# WWOL_main.net
KiCad netlist of a schematic drawn in Altium Designer
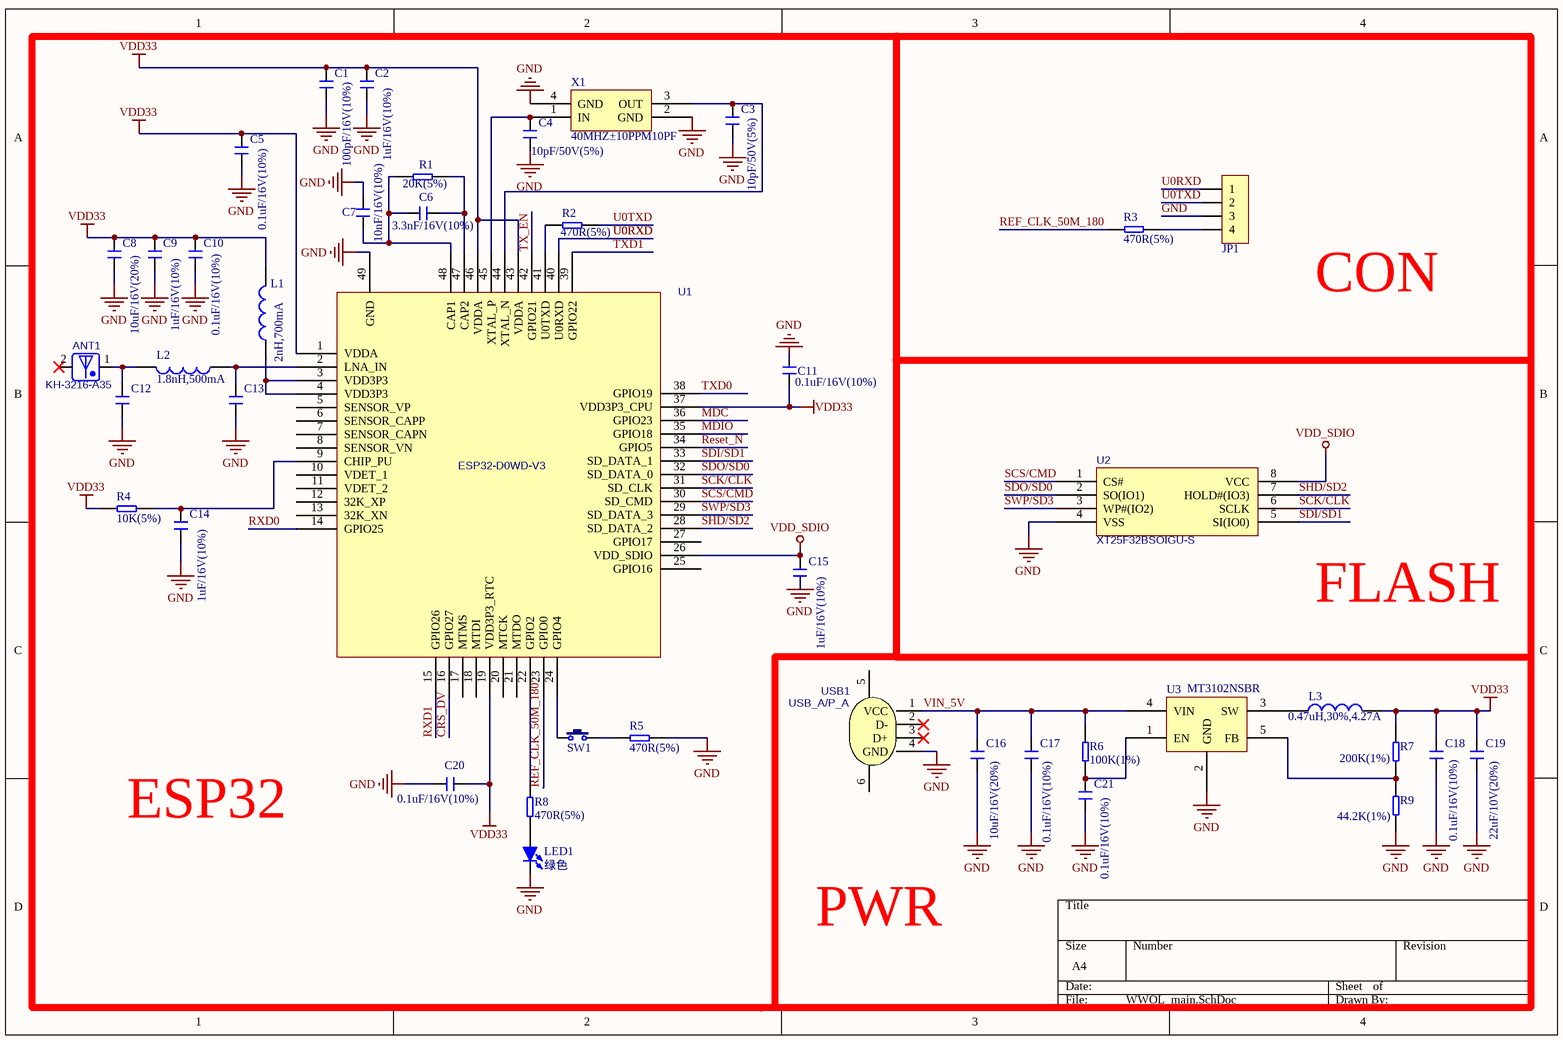
[diagram p0: WWOL_main.SchDoc]

(export (version "E")
  (design (tool "Eeschema 10.0.6"))
  (components
    (comp (ref "ANT1")
      (value "KH-3216-A35")
      (footprint "ANT-SMD-2_L3.2-W1.6-C504002")
      (description "金航标 KH-3216-A35")
      (fields (field (name "BOM_SUPPLIER PART") "C504002") (field (name "CONTRIBUTOR") "LCSC"))
      (libsource (lib "WWOL") (part "KH-3216-A35"))
    )
    (comp (ref "C1")
      (value "100pF/16V(10%)")
      (footprint "C0402")
      (description "无极性贴片电容")
      (fields (field (name "版权归属") "源创客"))
      (libsource (lib "WWOL") (part "C"))
    )
    (comp (ref "C2")
      (value "1uF/16V(10%)")
      (footprint "C0402")
      (description "无极性贴片电容")
      (fields (field (name "版权归属") "源创客"))
      (libsource (lib "WWOL") (part "C"))
    )
    (comp (ref "C3")
      (value "10pF/50V(5%)")
      (footprint "C0402")
      (description "无极性贴片电容")
      (fields (field (name "版权归属") "源创客"))
      (libsource (lib "WWOL") (part "C"))
    )
    (comp (ref "C4")
      (value "10pF/50V(5%)")
      (footprint "C0402")
      (description "无极性贴片电容")
      (fields (field (name "版权归属") "源创客"))
      (libsource (lib "WWOL") (part "C"))
    )
    (comp (ref "C5")
      (value "0.1uF/16V(10%)")
      (footprint "C0402")
      (description "无极性贴片电容")
      (fields (field (name "版权归属") "源创客"))
      (libsource (lib "WWOL") (part "C"))
    )
    (comp (ref "C6")
      (value "3.3nF/16V(10%)")
      (footprint "C0402")
      (description "无极性贴片电容")
      (fields (field (name "版权归属") "源创客"))
      (libsource (lib "WWOL") (part "C"))
    )
    (comp (ref "C7")
      (value "10nF/16V(10%)")
      (footprint "C0402")
      (description "无极性贴片电容")
      (fields (field (name "版权归属") "源创客"))
      (libsource (lib "WWOL") (part "C"))
    )
    (comp (ref "C8")
      (value "10uF/16V(20%)")
      (footprint "C0402")
      (description "无极性贴片电容")
      (fields (field (name "版权归属") "源创客"))
      (libsource (lib "WWOL") (part "C"))
    )
    (comp (ref "C9")
      (value "1uF/16V(10%)")
      (footprint "C0402")
      (description "无极性贴片电容")
      (fields (field (name "版权归属") "源创客"))
      (libsource (lib "WWOL") (part "C"))
    )
    (comp (ref "C10")
      (value "0.1uF/16V(10%)")
      (footprint "C0402")
      (description "无极性贴片电容")
      (fields (field (name "版权归属") "源创客"))
      (libsource (lib "WWOL") (part "C"))
    )
    (comp (ref "C11")
      (value "0.1uF/16V(10%)")
      (footprint "C0402")
      (description "无极性贴片电容")
      (fields (field (name "版权归属") "源创客"))
      (libsource (lib "WWOL") (part "C"))
    )
    (comp (ref "C12")
      (value "~")
      (footprint "C0402")
      (description "无极性贴片电容")
      (fields (field (name "版权归属") "源创客"))
      (libsource (lib "WWOL") (part "C"))
    )
    (comp (ref "C13")
      (value "~")
      (footprint "C0402")
      (description "无极性贴片电容")
      (fields (field (name "版权归属") "源创客"))
      (libsource (lib "WWOL") (part "C"))
    )
    (comp (ref "C14")
      (value "1uF/16V(10%)")
      (footprint "C0402")
      (description "无极性贴片电容")
      (fields (field (name "版权归属") "源创客"))
      (libsource (lib "WWOL") (part "C"))
    )
    (comp (ref "C15")
      (value "1uF/16V(10%)")
      (footprint "C0402")
      (description "无极性贴片电容")
      (fields (field (name "版权归属") "源创客"))
      (libsource (lib "WWOL") (part "C"))
    )
    (comp (ref "C16")
      (value "10uF/16V(20%)")
      (footprint "C0402")
      (description "无极性贴片电容")
      (fields (field (name "版权归属") "源创客"))
      (libsource (lib "WWOL") (part "C"))
    )
    (comp (ref "C17")
      (value "0.1uF/16V(10%)")
      (footprint "C0402")
      (description "无极性贴片电容")
      (fields (field (name "版权归属") "源创客"))
      (libsource (lib "WWOL") (part "C"))
    )
    (comp (ref "C18")
      (value "0.1uF/16V(10%)")
      (footprint "C0402")
      (description "无极性贴片电容")
      (fields (field (name "版权归属") "源创客"))
      (libsource (lib "WWOL") (part "C"))
    )
    (comp (ref "C19")
      (value "22uF/10V(20%)")
      (footprint "C0402")
      (description "无极性贴片电容")
      (fields (field (name "版权归属") "源创客"))
      (libsource (lib "WWOL") (part "C"))
    )
    (comp (ref "C20")
      (value "0.1uF/16V(10%)")
      (footprint "C0402")
      (description "无极性贴片电容")
      (fields (field (name "版权归属") "源创客"))
      (libsource (lib "WWOL") (part "C"))
    )
    (comp (ref "C21")
      (value "0.1uF/16V(10%)")
      (footprint "C0402")
      (description "无极性贴片电容")
      (fields (field (name "版权归属") "源创客"))
      (libsource (lib "WWOL") (part "C"))
    )
    (comp (ref "JP1")
      (value "HDR-1X4")
      (footprint "HDR2.54-LI-4P")
      (description "4P接插件")
      (fields (field (name "版权归属") "源创客"))
      (libsource (lib "WWOL") (part "Header 4"))
    )
    (comp (ref "L1")
      (value "2nH,700mA")
      (footprint "L0402")
      (description "小功率贴片电感")
      (libsource (lib "WWOL") (part "L"))
    )
    (comp (ref "L2")
      (value "1.8nH,500mA")
      (footprint "L0402")
      (description "小功率贴片电感")
      (libsource (lib "WWOL") (part "L"))
    )
    (comp (ref "L3")
      (value "0.47uH,30%,4.27A")
      (footprint "NR2520")
      (description "muRata(村田) DFE252012F-4R7M=P2")
      (libsource (lib "WWOL") (part "L"))
    )
    (comp (ref "LED1")
      (value "绿色")
      (footprint "LED 0402G")
      (description "贴片LED")
      (fields (field (name "版权归属") "源创客"))
      (libsource (lib "WWOL") (part "LED-SMD"))
    )
    (comp (ref "R1")
      (value "20K(5%)")
      (footprint "R0402")
      (description "贴片电阻")
      (libsource (lib "WWOL") (part "R"))
    )
    (comp (ref "R2")
      (value "470R(5%)")
      (footprint "R0402")
      (description "贴片电阻")
      (libsource (lib "WWOL") (part "R"))
    )
    (comp (ref "R3")
      (value "470R(5%)")
      (footprint "R0402")
      (description "贴片电阻")
      (libsource (lib "WWOL") (part "R"))
    )
    (comp (ref "R4")
      (value "10K(5%)")
      (footprint "R0402")
      (description "贴片电阻")
      (libsource (lib "WWOL") (part "R"))
    )
    (comp (ref "R5")
      (value "470R(5%)")
      (footprint "R0402")
      (description "贴片电阻")
      (libsource (lib "WWOL") (part "R"))
    )
    (comp (ref "R6")
      (value "100K(1%)")
      (footprint "R0402")
      (description "贴片电阻")
      (libsource (lib "WWOL") (part "R"))
    )
    (comp (ref "R7")
      (value "200K(1%)")
      (footprint "R0402")
      (description "贴片电阻")
      (libsource (lib "WWOL") (part "R"))
    )
    (comp (ref "R8")
      (value "470R(5%)")
      (footprint "R0402")
      (description "贴片电阻")
      (libsource (lib "WWOL") (part "R"))
    )
    (comp (ref "R9")
      (value "44.2K(1%)")
      (footprint "R0402")
      (description "贴片电阻")
      (libsource (lib "WWOL") (part "R"))
    )
    (comp (ref "SW1")
      (value "TSW SMD-3*6*2.5")
      (footprint "TSW SMD-3*6*2.5")
      (description "3x6轻触开关")
      (fields (field (name "版权归属") "源创客"))
      (libsource (lib "WWOL") (part "TSW 3x6"))
    )
    (comp (ref "U1")
      (value "ESP32-D0WD-V3")
      (footprint "QFN35P500X500X90_HS-49N")
      (fields (field (name "BOM_SUPPLIER PART") "C967021") (field (name "CONTRIBUTOR") "LCSC"))
      (libsource (lib "WWOL") (part "ESP32-D0WD-V3"))
    )
    (comp (ref "U2")
      (value "XT25F32BSOIGU-S")
      (footprint "SOP127P600X175-8N")
      (description "spi flash")
      (fields (field (name "BOM_SUPPLIER PART") "C558851") (field (name "CONTRIBUTOR") "LCSC"))
      (libsource (lib "WWOL") (part "XT25F32BSOIGU-S"))
    )
    (comp (ref "U3")
      (value "MT3102NSBR")
      (footprint "SOT95P280X145-5N")
      (description "开关电源")
      (libsource (lib "WWOL") (part "MT3102NSBR"))
    )
    (comp (ref "USB1")
      (value "USB_A/P_A")
      (footprint "USB_A/P_A")
      (description "精拓金 917-181A102ED60200")
      (fields
        (field (name "BOM_SUPPLIER PART") "C183610")
        (field (name "BOM_MANUFACTURER PART") "USB-07")
        (field (name "CONTRIBUTOR") "LCSC")
      )
      (libsource (lib "WWOL") (part "USB_A/P_A"))
    )
    (comp (ref "X1")
      (value "40MHZ±10PPM10PF")
      (footprint "SMD2520-4P")
      (description "无源晶振")
      (libsource (lib "WWOL") (part "XTAL-4P"))
    )
  )
  (nets
    (net (code "1") (name "/CRS_DV") (class "Default")
      (node (ref "U1") (pin "16") (pinfunction "GPIO27_16") (pintype "passive"))
    )
    (net (code "2") (name "/MDC") (class "Default")
      (node (ref "U1") (pin "36") (pinfunction "GPIO23_36") (pintype "passive"))
    )
    (net (code "3") (name "/MDIO") (class "Default")
      (node (ref "U1") (pin "35") (pinfunction "GPIO18_35") (pintype "passive"))
    )
    (net (code "4") (name "/REF_CLK_50M_180") (class "Default")
      (node (ref "R3") (pin "2") (pinfunction "2_2") (pintype "passive"))
      (node (ref "U1") (pin "23") (pinfunction "GPIO0_23") (pintype "passive"))
    )
    (net (code "5") (name "/RXD0") (class "Default")
      (node (ref "U1") (pin "14") (pinfunction "GPIO25_14") (pintype "passive"))
    )
    (net (code "6") (name "/RXD1") (class "Default")
      (node (ref "U1") (pin "15") (pinfunction "GPIO26_15") (pintype "passive"))
    )
    (net (code "7") (name "/Reset_N") (class "Default")
      (node (ref "U1") (pin "34") (pinfunction "GPIO5_34") (pintype "passive"))
    )
    (net (code "8") (name "/SCK{slash}CLK") (class "Default")
      (node (ref "U1") (pin "31") (pinfunction "SD_CLK_31") (pintype "passive"))
      (node (ref "U2") (pin "6") (pinfunction "SCLK_6") (pintype "passive"))
    )
    (net (code "9") (name "/SCS{slash}CMD") (class "Default")
      (node (ref "U1") (pin "30") (pinfunction "SD_CMD_30") (pintype "passive"))
      (node (ref "U2") (pin "1") (pinfunction "CS#_1") (pintype "passive"))
    )
    (net (code "10") (name "/SDI{slash}SD1") (class "Default")
      (node (ref "U1") (pin "33") (pinfunction "SD_DATA_1_33") (pintype "passive"))
      (node (ref "U2") (pin "5") (pinfunction "SI(IO0)_5") (pintype "passive"))
    )
    (net (code "11") (name "/SDO{slash}SD0") (class "Default")
      (node (ref "U1") (pin "32") (pinfunction "SD_DATA_0_32") (pintype "passive"))
      (node (ref "U2") (pin "2") (pinfunction "SO(IO1)_2") (pintype "passive"))
    )
    (net (code "12") (name "/SHD{slash}SD2") (class "Default")
      (node (ref "U1") (pin "28") (pinfunction "SD_DATA_2_28") (pintype "passive"))
      (node (ref "U2") (pin "7") (pinfunction "HOLD#(IO3)_7") (pintype "passive"))
    )
    (net (code "13") (name "/SWP{slash}SD3") (class "Default")
      (node (ref "U1") (pin "29") (pinfunction "SD_DATA_3_29") (pintype "passive"))
      (node (ref "U2") (pin "3") (pinfunction "WP#(IO2)_3") (pintype "passive"))
    )
    (net (code "14") (name "/TXD0") (class "Default")
      (node (ref "U1") (pin "38") (pinfunction "GPIO19_38") (pintype "passive"))
    )
    (net (code "15") (name "/TXD1") (class "Default")
      (node (ref "U1") (pin "39") (pinfunction "GPIO22_39") (pintype "passive"))
    )
    (net (code "16") (name "/TX_EN") (class "Default")
      (node (ref "U1") (pin "42") (pinfunction "GPIO21_42") (pintype "passive"))
    )
    (net (code "17") (name "/U0RXD") (class "Default")
      (node (ref "JP1") (pin "1") (pinfunction "1_1") (pintype "passive"))
      (node (ref "U1") (pin "40") (pinfunction "U0RXD_40") (pintype "passive"))
    )
    (net (code "18") (name "/U0TXD") (class "Default")
      (node (ref "JP1") (pin "2") (pinfunction "2_2") (pintype "passive"))
      (node (ref "R2") (pin "1") (pinfunction "1_1") (pintype "passive"))
    )
    (net (code "19") (name "/VIN_5V") (class "Default")
      (node (ref "C16") (pin "2") (pinfunction "2_2") (pintype "passive"))
      (node (ref "C17") (pin "2") (pinfunction "2_2") (pintype "passive"))
      (node (ref "R6") (pin "2") (pinfunction "2_2") (pintype "passive"))
      (node (ref "U3") (pin "4") (pinfunction "VIN_4") (pintype "passive"))
      (node (ref "USB1") (pin "1") (pinfunction "VCC_1") (pintype "passive"))
    )
    (net (code "20") (name "GND") (class "Default")
      (node (ref "C1") (pin "1") (pinfunction "1_1") (pintype "passive"))
      (node (ref "C10") (pin "1") (pinfunction "1_1") (pintype "passive"))
      (node (ref "C11") (pin "1") (pinfunction "1_1") (pintype "passive"))
      (node (ref "C12") (pin "1") (pinfunction "1_1") (pintype "passive"))
      (node (ref "C13") (pin "1") (pinfunction "1_1") (pintype "passive"))
      (node (ref "C14") (pin "1") (pinfunction "1_1") (pintype "passive"))
      (node (ref "C15") (pin "1") (pinfunction "1_1") (pintype "passive"))
      (node (ref "C16") (pin "1") (pinfunction "1_1") (pintype "passive"))
      (node (ref "C17") (pin "1") (pinfunction "1_1") (pintype "passive"))
      (node (ref "C18") (pin "1") (pinfunction "1_1") (pintype "passive"))
      (node (ref "C19") (pin "1") (pinfunction "1_1") (pintype "passive"))
      (node (ref "C2") (pin "1") (pinfunction "1_1") (pintype "passive"))
      (node (ref "C20") (pin "1") (pinfunction "1_1") (pintype "passive"))
      (node (ref "C21") (pin "1") (pinfunction "1_1") (pintype "passive"))
      (node (ref "C3") (pin "1") (pinfunction "1_1") (pintype "passive"))
      (node (ref "C4") (pin "1") (pinfunction "1_1") (pintype "passive"))
      (node (ref "C5") (pin "1") (pinfunction "1_1") (pintype "passive"))
      (node (ref "C7") (pin "2") (pinfunction "2_2") (pintype "passive"))
      (node (ref "C8") (pin "1") (pinfunction "1_1") (pintype "passive"))
      (node (ref "C9") (pin "1") (pinfunction "1_1") (pintype "passive"))
      (node (ref "JP1") (pin "3") (pinfunction "3_3") (pintype "passive"))
      (node (ref "LED1") (pin "2") (pinfunction "K_2") (pintype "passive"))
      (node (ref "R5") (pin "1") (pinfunction "1_1") (pintype "passive"))
      (node (ref "R9") (pin "1") (pinfunction "1_1") (pintype "passive"))
      (node (ref "U1") (pin "49") (pinfunction "GND_49") (pintype "passive"))
      (node (ref "U2") (pin "4") (pinfunction "VSS_4") (pintype "passive"))
      (node (ref "U3") (pin "2") (pinfunction "GND_2") (pintype "passive"))
      (node (ref "USB1") (pin "4") (pinfunction "GND_4") (pintype "passive"))
      (node (ref "X1") (pin "2") (pinfunction "GND_2") (pintype "passive"))
      (node (ref "X1") (pin "4") (pinfunction "GND_4") (pintype "passive"))
    )
    (net (code "21") (name "Net-(ANT1-Pad1)") (class "Default")
      (node (ref "ANT1") (pin "1") (pinfunction "1_1") (pintype "passive"))
      (node (ref "C12") (pin "2") (pinfunction "2_2") (pintype "passive"))
      (node (ref "L2") (pin "2") (pinfunction "2_2") (pintype "passive"))
    )
    (net (code "22") (name "Net-(JP1-Pad4)") (class "Default")
      (node (ref "JP1") (pin "4") (pinfunction "4_4") (pintype "passive"))
      (node (ref "R3") (pin "1") (pinfunction "1_1") (pintype "passive"))
    )
    (net (code "23") (name "Net-(L1-Pad1)") (class "Default")
      (node (ref "L1") (pin "1") (pinfunction "1_1") (pintype "passive"))
      (node (ref "U1") (pin "3") (pinfunction "VDD3P3_3") (pintype "passive"))
      (node (ref "U1") (pin "4") (pinfunction "VDD3P3_4") (pintype "passive"))
    )
    (net (code "24") (name "Net-(LED1-A)") (class "Default")
      (node (ref "LED1") (pin "1") (pinfunction "A_1") (pintype "passive"))
      (node (ref "R8") (pin "1") (pinfunction "1_1") (pintype "passive"))
    )
    (net (code "25") (name "Net-(R5-Pad2)") (class "Default")
      (node (ref "R5") (pin "2") (pinfunction "2_2") (pintype "passive"))
      (node (ref "SW1") (pin "2") (pinfunction "2_2") (pintype "passive"))
    )
    (net (code "26") (name "Net-(U1-CAP1)") (class "Default")
      (node (ref "C6") (pin "2") (pinfunction "2_2") (pintype "passive"))
      (node (ref "C7") (pin "1") (pinfunction "1_1") (pintype "passive"))
      (node (ref "R1") (pin "2") (pinfunction "2_2") (pintype "passive"))
      (node (ref "U1") (pin "48") (pinfunction "CAP1_48") (pintype "passive"))
    )
    (net (code "27") (name "Net-(U1-CAP2)") (class "Default")
      (node (ref "C6") (pin "1") (pinfunction "1_1") (pintype "passive"))
      (node (ref "R1") (pin "1") (pinfunction "1_1") (pintype "passive"))
      (node (ref "U1") (pin "47") (pinfunction "CAP2_47") (pintype "passive"))
    )
    (net (code "28") (name "Net-(U1-CHIP_PU)") (class "Default")
      (node (ref "C14") (pin "2") (pinfunction "2_2") (pintype "passive"))
      (node (ref "R4") (pin "1") (pinfunction "1_1") (pintype "passive"))
      (node (ref "U1") (pin "9") (pinfunction "CHIP_PU_9") (pintype "passive"))
    )
    (net (code "29") (name "Net-(U1-GPIO2)") (class "Default")
      (node (ref "R8") (pin "2") (pinfunction "2_2") (pintype "passive"))
      (node (ref "U1") (pin "22") (pinfunction "GPIO2_22") (pintype "passive"))
    )
    (net (code "30") (name "Net-(U1-GPIO4)") (class "Default")
      (node (ref "SW1") (pin "1") (pinfunction "1_1") (pintype "passive"))
      (node (ref "U1") (pin "24") (pinfunction "GPIO4_24") (pintype "passive"))
    )
    (net (code "31") (name "Net-(U1-LNA_IN)") (class "Default")
      (node (ref "C13") (pin "2") (pinfunction "2_2") (pintype "passive"))
      (node (ref "L2") (pin "1") (pinfunction "1_1") (pintype "passive"))
      (node (ref "U1") (pin "2") (pinfunction "LNA_IN_2") (pintype "passive"))
    )
    (net (code "32") (name "Net-(U1-U0TXD)") (class "Default")
      (node (ref "R2") (pin "2") (pinfunction "2_2") (pintype "passive"))
      (node (ref "U1") (pin "41") (pinfunction "U0TXD_41") (pintype "passive"))
    )
    (net (code "33") (name "Net-(U1-XTAL_N)") (class "Default")
      (node (ref "C3") (pin "2") (pinfunction "2_2") (pintype "passive"))
      (node (ref "U1") (pin "44") (pinfunction "XTAL_N_44") (pintype "passive"))
      (node (ref "X1") (pin "3") (pinfunction "OUT_3") (pintype "passive"))
    )
    (net (code "34") (name "Net-(U1-XTAL_P)") (class "Default")
      (node (ref "C4") (pin "2") (pinfunction "2_2") (pintype "passive"))
      (node (ref "U1") (pin "45") (pinfunction "XTAL_P_45") (pintype "passive"))
      (node (ref "X1") (pin "1") (pinfunction "IN_1") (pintype "passive"))
    )
    (net (code "35") (name "Net-(U3-EN)") (class "Default")
      (node (ref "C21") (pin "2") (pinfunction "2_2") (pintype "passive"))
      (node (ref "R6") (pin "1") (pinfunction "1_1") (pintype "passive"))
      (node (ref "U3") (pin "1") (pinfunction "EN_1") (pintype "passive"))
    )
    (net (code "36") (name "Net-(U3-FB)") (class "Default")
      (node (ref "R7") (pin "1") (pinfunction "1_1") (pintype "passive"))
      (node (ref "R9") (pin "2") (pinfunction "2_2") (pintype "passive"))
      (node (ref "U3") (pin "5") (pinfunction "FB_5") (pintype "passive"))
    )
    (net (code "37") (name "Net-(U3-SW)") (class "Default")
      (node (ref "L3") (pin "1") (pinfunction "1_1") (pintype "passive"))
      (node (ref "U3") (pin "3") (pinfunction "SW_3") (pintype "passive"))
    )
    (net (code "38") (name "VDD33") (class "Default")
      (node (ref "C1") (pin "2") (pinfunction "2_2") (pintype "passive"))
      (node (ref "C10") (pin "2") (pinfunction "2_2") (pintype "passive"))
      (node (ref "C11") (pin "2") (pinfunction "2_2") (pintype "passive"))
      (node (ref "C18") (pin "2") (pinfunction "2_2") (pintype "passive"))
      (node (ref "C19") (pin "2") (pinfunction "2_2") (pintype "passive"))
      (node (ref "C2") (pin "2") (pinfunction "2_2") (pintype "passive"))
      (node (ref "C20") (pin "2") (pinfunction "2_2") (pintype "passive"))
      (node (ref "C5") (pin "2") (pinfunction "2_2") (pintype "passive"))
      (node (ref "C8") (pin "2") (pinfunction "2_2") (pintype "passive"))
      (node (ref "C9") (pin "2") (pinfunction "2_2") (pintype "passive"))
      (node (ref "L1") (pin "2") (pinfunction "2_2") (pintype "passive"))
      (node (ref "L3") (pin "2") (pinfunction "2_2") (pintype "passive"))
      (node (ref "R4") (pin "2") (pinfunction "2_2") (pintype "passive"))
      (node (ref "R7") (pin "2") (pinfunction "2_2") (pintype "passive"))
      (node (ref "U1") (pin "1") (pinfunction "VDDA_1") (pintype "passive"))
      (node (ref "U1") (pin "19") (pinfunction "VDD3P3_RTC_19") (pintype "passive"))
      (node (ref "U1") (pin "37") (pinfunction "VDD3P3_CPU_37") (pintype "passive"))
      (node (ref "U1") (pin "43") (pinfunction "VDDA_43") (pintype "passive"))
      (node (ref "U1") (pin "46") (pinfunction "VDDA_46") (pintype "passive"))
    )
    (net (code "39") (name "VDD_SDIO") (class "Default")
      (node (ref "C15") (pin "2") (pinfunction "2_2") (pintype "passive"))
      (node (ref "U1") (pin "26") (pinfunction "VDD_SDIO_26") (pintype "passive"))
      (node (ref "U2") (pin "8") (pinfunction "VCC_8") (pintype "passive"))
    )
    (net (code "40") (name "unconnected-(ANT1-Pad2)") (class "Default")
      (node (ref "ANT1") (pin "2") (pinfunction "2_2") (pintype "passive+no_connect"))
    )
    (net (code "41") (name "unconnected-(U1-32K_XN-Pad13)") (class "Default")
      (node (ref "U1") (pin "13") (pinfunction "32K_XN_13") (pintype "passive"))
    )
    (net (code "42") (name "unconnected-(U1-32K_XP-Pad12)") (class "Default")
      (node (ref "U1") (pin "12") (pinfunction "32K_XP_12") (pintype "passive"))
    )
    (net (code "43") (name "unconnected-(U1-GPIO16-Pad25)") (class "Default")
      (node (ref "U1") (pin "25") (pinfunction "GPIO16_25") (pintype "passive"))
    )
    (net (code "44") (name "unconnected-(U1-GPIO17-Pad27)") (class "Default")
      (node (ref "U1") (pin "27") (pinfunction "GPIO17_27") (pintype "passive"))
    )
    (net (code "45") (name "unconnected-(U1-MTCK-Pad20)") (class "Default")
      (node (ref "U1") (pin "20") (pinfunction "MTCK_20") (pintype "passive"))
    )
    (net (code "46") (name "unconnected-(U1-MTDI-Pad18)") (class "Default")
      (node (ref "U1") (pin "18") (pinfunction "MTDI_18") (pintype "passive"))
    )
    (net (code "47") (name "unconnected-(U1-MTDO-Pad21)") (class "Default")
      (node (ref "U1") (pin "21") (pinfunction "MTDO_21") (pintype "passive"))
    )
    (net (code "48") (name "unconnected-(U1-MTMS-Pad17)") (class "Default")
      (node (ref "U1") (pin "17") (pinfunction "MTMS_17") (pintype "passive"))
    )
    (net (code "49") (name "unconnected-(U1-SENSOR_CAPN-Pad7)") (class "Default")
      (node (ref "U1") (pin "7") (pinfunction "SENSOR_CAPN_7") (pintype "passive"))
    )
    (net (code "50") (name "unconnected-(U1-SENSOR_CAPP-Pad6)") (class "Default")
      (node (ref "U1") (pin "6") (pinfunction "SENSOR_CAPP_6") (pintype "passive"))
    )
    (net (code "51") (name "unconnected-(U1-SENSOR_VN-Pad8)") (class "Default")
      (node (ref "U1") (pin "8") (pinfunction "SENSOR_VN_8") (pintype "passive"))
    )
    (net (code "52") (name "unconnected-(U1-SENSOR_VP-Pad5)") (class "Default")
      (node (ref "U1") (pin "5") (pinfunction "SENSOR_VP_5") (pintype "passive"))
    )
    (net (code "53") (name "unconnected-(U1-VDET_1-Pad10)") (class "Default")
      (node (ref "U1") (pin "10") (pinfunction "VDET_1_10") (pintype "passive"))
    )
    (net (code "54") (name "unconnected-(U1-VDET_2-Pad11)") (class "Default")
      (node (ref "U1") (pin "11") (pinfunction "VDET_2_11") (pintype "passive"))
    )
    (net (code "55") (name "unconnected-(USB1-D+-Pad3)") (class "Default")
      (node (ref "USB1") (pin "3") (pinfunction "D+_3") (pintype "passive+no_connect"))
    )
    (net (code "56") (name "unconnected-(USB1-D--Pad2)") (class "Default")
      (node (ref "USB1") (pin "2") (pinfunction "D-_2") (pintype "passive+no_connect"))
    )
    (net (code "57") (name "unconnected-(USB1-Pad5)") (class "Default")
      (node (ref "USB1") (pin "5") (pinfunction "5_5") (pintype "passive"))
    )
    (net (code "58") (name "unconnected-(USB1-Pad6)") (class "Default")
      (node (ref "USB1") (pin "6") (pinfunction "6_6") (pintype "passive"))
    )
  )
)
